# LPC1115_4TE_TOP.net
KiCad netlist of a schematic drawn in EAGLE
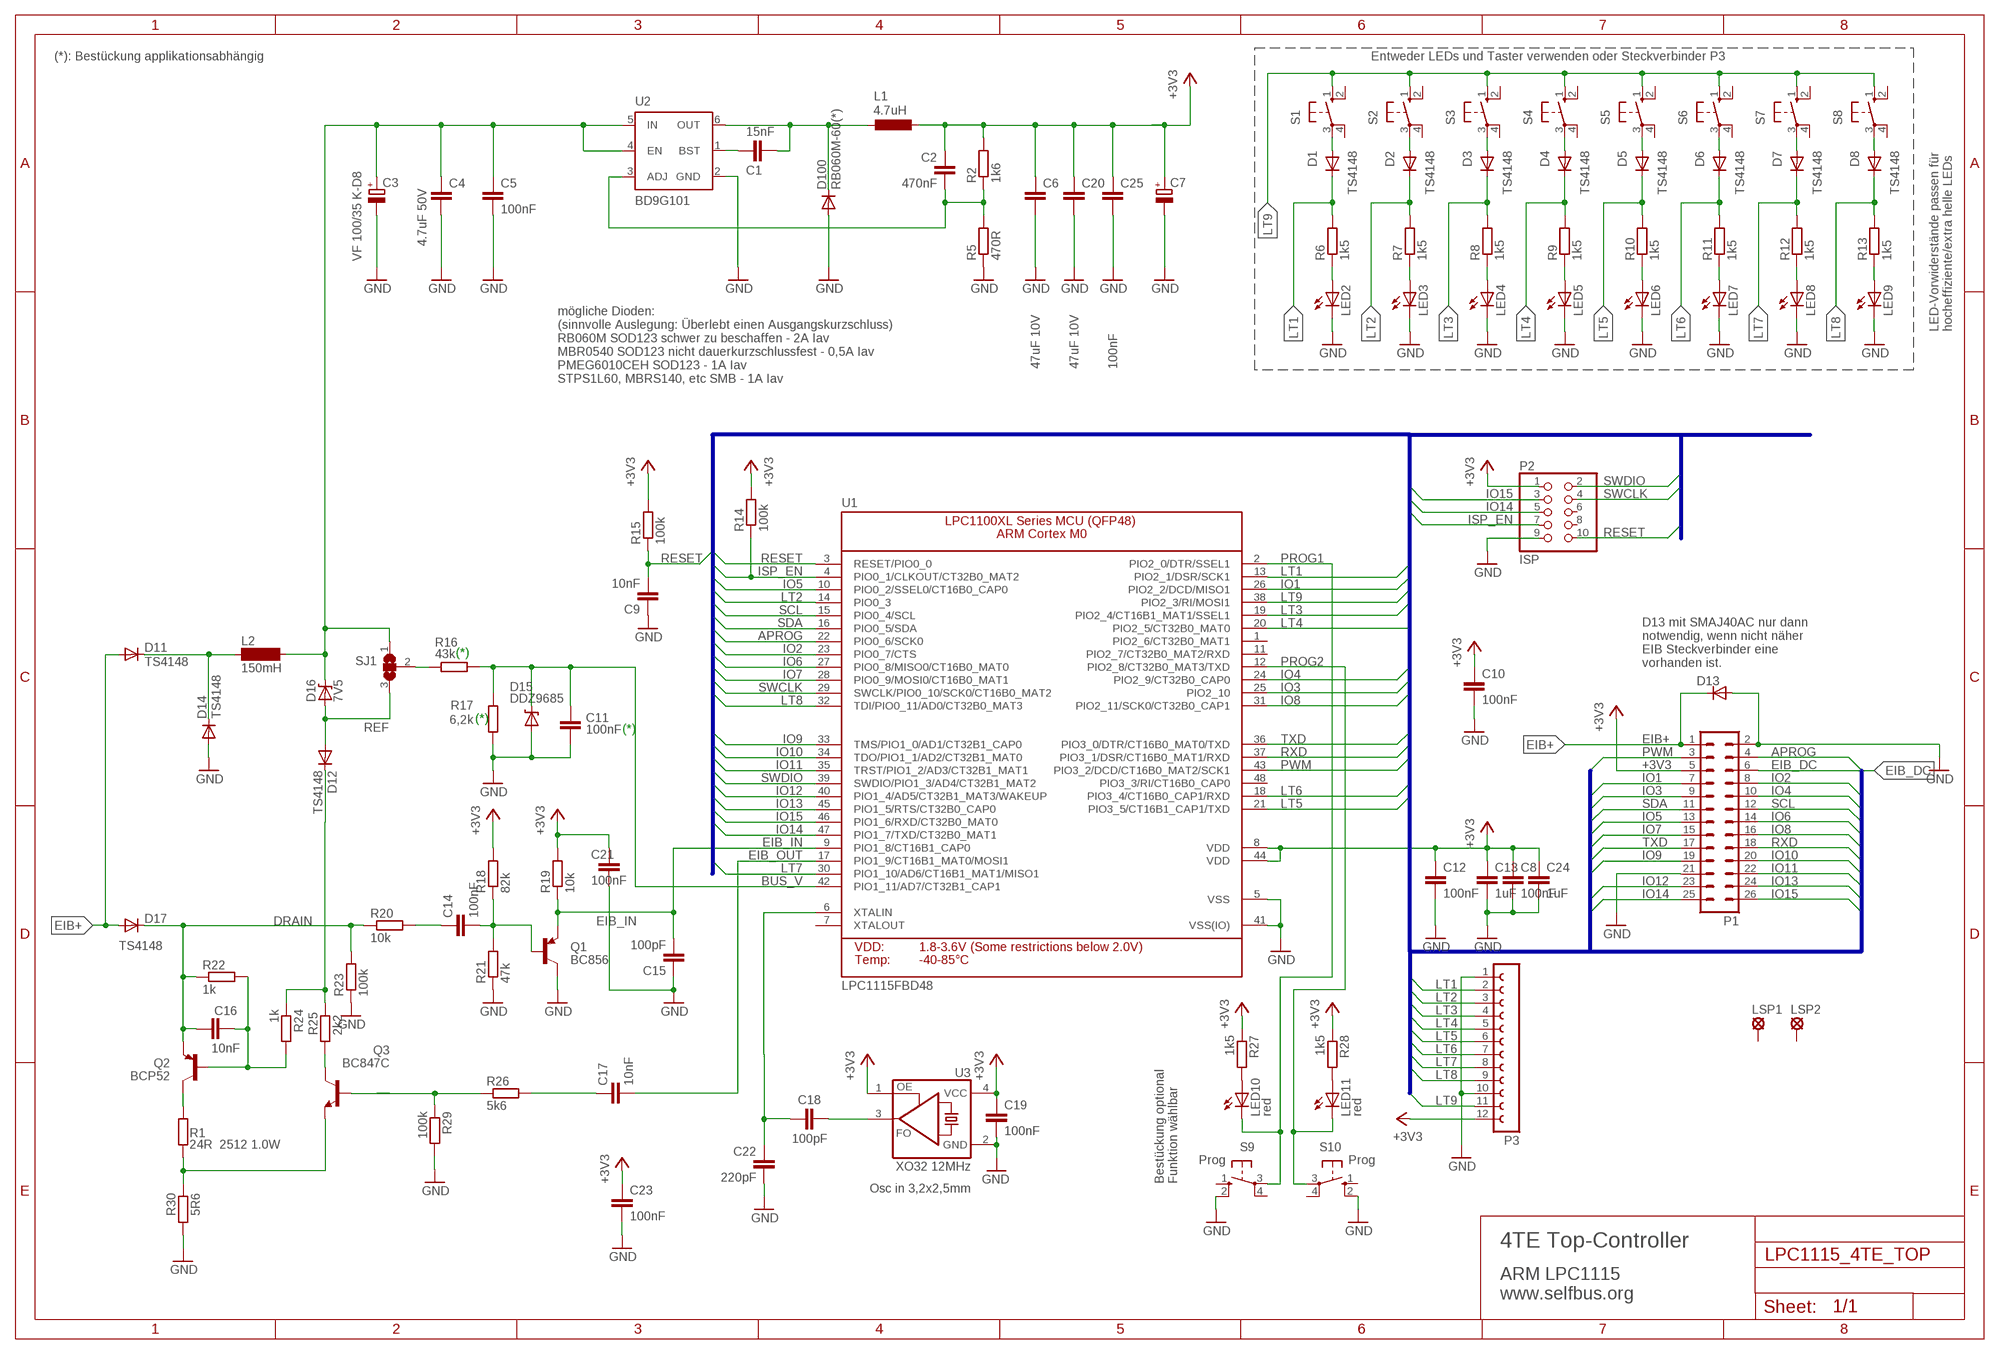
[diagram p0: schematic, sheet 1]

(export (version "E")
  (design (tool "Eeschema 10.0.6"))
  (components
    (comp (ref "C1")
      (value "15nF")
      (footprint "eagle-import:C0805")
      (libsource (lib "eagle-import") (part "C-EUC0805"))
    )
    (comp (ref "C2")
      (value "470nF")
      (footprint "eagle-import:C0805")
      (libsource (lib "eagle-import") (part "C-EUC0805"))
    )
    (comp (ref "C3")
      (value "VF 100/35 K-D8")
      (footprint "eagle-import:ESMD-D")
      (libsource (lib "eagle-import") (part "CPOL-EUESMD-D"))
    )
    (comp (ref "C4")
      (value "4.7uF 50V")
      (footprint "eagle-import:C0805")
      (libsource (lib "eagle-import") (part "C-EUC0805"))
    )
    (comp (ref "C5")
      (value "100nF")
      (footprint "eagle-import:C0805")
      (libsource (lib "eagle-import") (part "C-EUC0805"))
    )
    (comp (ref "C6")
      (value "47uF 10V")
      (footprint "eagle-import:C0805")
      (libsource (lib "eagle-import") (part "C-EUC0805"))
    )
    (comp (ref "C7")
      (value "100uF")
      (footprint "eagle-import:ESMD-D")
      (libsource (lib "eagle-import") (part "CPOL-EUESMD-D"))
    )
    (comp (ref "C8")
      (value "100nF")
      (footprint "eagle-import:C0805")
      (libsource (lib "eagle-import") (part "C-EUC0805"))
    )
    (comp (ref "C9")
      (value "10nF")
      (footprint "eagle-import:C0805")
      (libsource (lib "eagle-import") (part "C-EUC0805"))
    )
    (comp (ref "C10")
      (value "100nF")
      (footprint "eagle-import:C0805")
      (libsource (lib "eagle-import") (part "C-EUC0805"))
    )
    (comp (ref "C11")
      (value "100nF")
      (footprint "eagle-import:C0805")
      (libsource (lib "eagle-import") (part "C-EUC0805"))
    )
    (comp (ref "C12")
      (value "100nF")
      (footprint "eagle-import:C0805")
      (libsource (lib "eagle-import") (part "C-EUC0805"))
    )
    (comp (ref "C13")
      (value "1uF")
      (footprint "eagle-import:C0805")
      (libsource (lib "eagle-import") (part "C-EUC0805"))
    )
    (comp (ref "C14")
      (value "100nF")
      (footprint "eagle-import:C0805")
      (libsource (lib "eagle-import") (part "C-EUC0805"))
    )
    (comp (ref "C15")
      (value "100pF")
      (footprint "eagle-import:C0805")
      (libsource (lib "eagle-import") (part "C-EUC0805"))
    )
    (comp (ref "C16")
      (value "10nF")
      (footprint "eagle-import:C0805")
      (libsource (lib "eagle-import") (part "C-EUC0805"))
    )
    (comp (ref "C17")
      (value "10nF")
      (footprint "eagle-import:C0805")
      (libsource (lib "eagle-import") (part "C-EUC0805"))
    )
    (comp (ref "C18")
      (value "100pF")
      (footprint "eagle-import:C0805")
      (libsource (lib "eagle-import") (part "C-EUC0805"))
    )
    (comp (ref "C19")
      (value "100nF")
      (footprint "eagle-import:C0805")
      (libsource (lib "eagle-import") (part "C-EUC0805"))
    )
    (comp (ref "C20")
      (value "47uF 10V")
      (footprint "eagle-import:C0805")
      (libsource (lib "eagle-import") (part "C-EUC0805"))
    )
    (comp (ref "C21")
      (value "100nF")
      (footprint "eagle-import:C0805")
      (libsource (lib "eagle-import") (part "C-EUC0805"))
    )
    (comp (ref "C22")
      (value "220pF")
      (footprint "eagle-import:C0805")
      (libsource (lib "eagle-import") (part "C-EUC0805"))
    )
    (comp (ref "C23")
      (value "100nF")
      (footprint "eagle-import:C0805")
      (libsource (lib "eagle-import") (part "C-EUC0805"))
    )
    (comp (ref "C24")
      (value "1uF")
      (footprint "eagle-import:C0805")
      (libsource (lib "eagle-import") (part "C-EUC0805"))
    )
    (comp (ref "C25")
      (value "100nF")
      (footprint "eagle-import:C1206")
      (libsource (lib "eagle-import") (part "C-EUC1206"))
    )
    (comp (ref "D1")
      (value "TS4148")
      (footprint "eagle-import:D0805")
      (libsource (lib "eagle-import") (part "DIODE-D0805"))
    )
    (comp (ref "D2")
      (value "TS4148")
      (footprint "eagle-import:D0805")
      (libsource (lib "eagle-import") (part "DIODE-D0805"))
    )
    (comp (ref "D3")
      (value "TS4148")
      (footprint "eagle-import:D0805")
      (libsource (lib "eagle-import") (part "DIODE-D0805"))
    )
    (comp (ref "D4")
      (value "TS4148")
      (footprint "eagle-import:D0805")
      (libsource (lib "eagle-import") (part "DIODE-D0805"))
    )
    (comp (ref "D5")
      (value "TS4148")
      (footprint "eagle-import:D0805")
      (libsource (lib "eagle-import") (part "DIODE-D0805"))
    )
    (comp (ref "D6")
      (value "TS4148")
      (footprint "eagle-import:D0805")
      (libsource (lib "eagle-import") (part "DIODE-D0805"))
    )
    (comp (ref "D7")
      (value "TS4148")
      (footprint "eagle-import:D0805")
      (libsource (lib "eagle-import") (part "DIODE-D0805"))
    )
    (comp (ref "D8")
      (value "TS4148")
      (footprint "eagle-import:D0805")
      (libsource (lib "eagle-import") (part "DIODE-D0805"))
    )
    (comp (ref "D11")
      (value "TS4148")
      (footprint "eagle-import:D0805")
      (libsource (lib "eagle-import") (part "DIODE-D0805"))
    )
    (comp (ref "D12")
      (value "TS4148")
      (footprint "eagle-import:D0805")
      (libsource (lib "eagle-import") (part "DIODE-D0805"))
    )
    (comp (ref "D13")
      (value "SMAJ40AC")
      (footprint "eagle-import:SMB")
      (libsource (lib "eagle-import") (part "D-SMB"))
    )
    (comp (ref "D14")
      (value "TS4148")
      (footprint "eagle-import:D0805")
      (libsource (lib "eagle-import") (part "DIODE-D0805"))
    )
    (comp (ref "D15")
      (value "DDZ9685")
      (footprint "eagle-import:SOD-123")
      (libsource (lib "eagle-import") (part "DIODE-ZENERSOD-123"))
    )
    (comp (ref "D16")
      (value "7V5")
      (footprint "eagle-import:SOD-123")
      (libsource (lib "eagle-import") (part "DIODE-ZENERSOD-123"))
    )
    (comp (ref "D17")
      (value "TS4148")
      (footprint "eagle-import:D0805")
      (libsource (lib "eagle-import") (part "DIODE-D0805"))
    )
    (comp (ref "D100")
      (value "RB060M-60(*)")
      (footprint "eagle-import:SOD123")
      (libsource (lib "eagle-import") (part "DIODE-SOD123"))
    )
    (comp (ref "L1")
      (value "4.7uH")
      (footprint "eagle-import:L4532P")
      (libsource (lib "eagle-import") (part "L-EUL4532P"))
    )
    (comp (ref "L2")
      (value "150mH")
      (footprint "eagle-import:BS11_LIEGEND")
      (libsource (lib "eagle-import") (part "SD12BS11_LIEGEND"))
    )
    (comp (ref "LED2")
      (value "LEDSMT1206")
      (footprint "eagle-import:1206")
      (libsource (lib "eagle-import") (part "LEDSMT1206"))
    )
    (comp (ref "LED3")
      (value "LEDSMT1206")
      (footprint "eagle-import:1206")
      (libsource (lib "eagle-import") (part "LEDSMT1206"))
    )
    (comp (ref "LED4")
      (value "LEDSMT1206")
      (footprint "eagle-import:1206")
      (libsource (lib "eagle-import") (part "LEDSMT1206"))
    )
    (comp (ref "LED5")
      (value "LEDSMT1206")
      (footprint "eagle-import:1206")
      (libsource (lib "eagle-import") (part "LEDSMT1206"))
    )
    (comp (ref "LED6")
      (value "LEDSMT1206")
      (footprint "eagle-import:1206")
      (libsource (lib "eagle-import") (part "LEDSMT1206"))
    )
    (comp (ref "LED7")
      (value "LEDSMT1206")
      (footprint "eagle-import:1206")
      (libsource (lib "eagle-import") (part "LEDSMT1206"))
    )
    (comp (ref "LED8")
      (value "LEDSMT1206")
      (footprint "eagle-import:1206")
      (libsource (lib "eagle-import") (part "LEDSMT1206"))
    )
    (comp (ref "LED9")
      (value "LEDSMT1206")
      (footprint "eagle-import:1206")
      (libsource (lib "eagle-import") (part "LEDSMT1206"))
    )
    (comp (ref "LED10")
      (value "red")
      (footprint "eagle-import:1206")
      (libsource (lib "eagle-import") (part "LEDSMT1206"))
    )
    (comp (ref "LED11")
      (value "red")
      (footprint "eagle-import:1206")
      (libsource (lib "eagle-import") (part "LEDSMT1206"))
    )
    (comp (ref "LSP1")
      (value "SE13_SM")
      (footprint "eagle-import:SE13_SM")
      (libsource (lib "eagle-import") (part "SE13_SM"))
    )
    (comp (ref "LSP2")
      (value "SE13_SM")
      (footprint "eagle-import:SE13_SM")
      (libsource (lib "eagle-import") (part "SE13_SM"))
    )
    (comp (ref "P1")
      (value "ML26")
      (footprint "eagle-import:ML26")
      (libsource (lib "eagle-import") (part "ML26"))
    )
    (comp (ref "P2")
      (value "ISP")
      (footprint "eagle-import:2X05M")
      (libsource (lib "eagle-import") (part "PINHD-2X05_2.00"))
    )
    (comp (ref "P3")
      (value "FE12-1")
      (footprint "eagle-import:FE12")
      (libsource (lib "eagle-import") (part "FE12-1"))
    )
    (comp (ref "Q1")
      (value "BC856")
      (footprint "eagle-import:SOT23-BEC")
      (libsource (lib "eagle-import") (part "BC856SMDB"))
    )
    (comp (ref "Q2")
      (value "BCP52")
      (footprint "eagle-import:SOT223")
      (libsource (lib "eagle-import") (part "FZT753SMD"))
    )
    (comp (ref "Q3")
      (value "BC847C")
      (footprint "eagle-import:SOT23")
      (libsource (lib "eagle-import") (part "BC847"))
    )
    (comp (ref "R1")
      (value "24R 2512 1.0W")
      (footprint "eagle-import:R2512")
      (libsource (lib "eagle-import") (part "R-EU_R2512"))
    )
    (comp (ref "R2")
      (value "1k6")
      (footprint "eagle-import:R0805")
      (libsource (lib "eagle-import") (part "R-EU_R0805"))
    )
    (comp (ref "R5")
      (value "470R")
      (footprint "eagle-import:R0805")
      (libsource (lib "eagle-import") (part "R-EU_R0805"))
    )
    (comp (ref "R6")
      (value "1k5")
      (footprint "eagle-import:R0805")
      (libsource (lib "eagle-import") (part "R-EU_R0805"))
    )
    (comp (ref "R7")
      (value "1k5")
      (footprint "eagle-import:R0805")
      (libsource (lib "eagle-import") (part "R-EU_R0805"))
    )
    (comp (ref "R8")
      (value "1k5")
      (footprint "eagle-import:R0805")
      (libsource (lib "eagle-import") (part "R-EU_R0805"))
    )
    (comp (ref "R9")
      (value "1k5")
      (footprint "eagle-import:R0805")
      (libsource (lib "eagle-import") (part "R-EU_R0805"))
    )
    (comp (ref "R10")
      (value "1k5")
      (footprint "eagle-import:R0805")
      (libsource (lib "eagle-import") (part "R-EU_R0805"))
    )
    (comp (ref "R11")
      (value "1k5")
      (footprint "eagle-import:R0805")
      (libsource (lib "eagle-import") (part "R-EU_R0805"))
    )
    (comp (ref "R12")
      (value "1k5")
      (footprint "eagle-import:R0805")
      (libsource (lib "eagle-import") (part "R-EU_R0805"))
    )
    (comp (ref "R13")
      (value "1k5")
      (footprint "eagle-import:R0805")
      (libsource (lib "eagle-import") (part "R-EU_R0805"))
    )
    (comp (ref "R14")
      (value "100k")
      (footprint "eagle-import:R0805")
      (libsource (lib "eagle-import") (part "R-EU_R0805"))
    )
    (comp (ref "R15")
      (value "100k")
      (footprint "eagle-import:R0805")
      (libsource (lib "eagle-import") (part "R-EU_R0805"))
    )
    (comp (ref "R16")
      (value "43k")
      (footprint "eagle-import:R0805")
      (libsource (lib "eagle-import") (part "R-EU_R0805"))
    )
    (comp (ref "R17")
      (value "6,2k")
      (footprint "eagle-import:R0805")
      (libsource (lib "eagle-import") (part "R-EU_R0805"))
    )
    (comp (ref "R18")
      (value "82k")
      (footprint "eagle-import:R0805")
      (libsource (lib "eagle-import") (part "R-EU_R0805"))
    )
    (comp (ref "R19")
      (value "10k")
      (footprint "eagle-import:R0805")
      (libsource (lib "eagle-import") (part "R-EU_R0805"))
    )
    (comp (ref "R20")
      (value "10k")
      (footprint "eagle-import:R0805")
      (libsource (lib "eagle-import") (part "R-EU_R0805"))
    )
    (comp (ref "R21")
      (value "47k")
      (footprint "eagle-import:R0805")
      (libsource (lib "eagle-import") (part "R-EU_R0805"))
    )
    (comp (ref "R22")
      (value "1k")
      (footprint "eagle-import:R0805")
      (libsource (lib "eagle-import") (part "R-EU_R0805"))
    )
    (comp (ref "R23")
      (value "100k")
      (footprint "eagle-import:R0805")
      (libsource (lib "eagle-import") (part "R-EU_R0805"))
    )
    (comp (ref "R24")
      (value "1k")
      (footprint "eagle-import:R0805")
      (libsource (lib "eagle-import") (part "R-EU_R0805"))
    )
    (comp (ref "R25")
      (value "2k2")
      (footprint "eagle-import:R0805")
      (libsource (lib "eagle-import") (part "R-EU_R0805"))
    )
    (comp (ref "R26")
      (value "5k6")
      (footprint "eagle-import:R0805")
      (libsource (lib "eagle-import") (part "R-EU_R0805"))
    )
    (comp (ref "R27")
      (value "1k5")
      (footprint "eagle-import:R0805")
      (libsource (lib "eagle-import") (part "R-EU_R0805"))
    )
    (comp (ref "R28")
      (value "1k5")
      (footprint "eagle-import:R0805")
      (libsource (lib "eagle-import") (part "R-EU_R0805"))
    )
    (comp (ref "R29")
      (value "100k")
      (footprint "eagle-import:R0805")
      (libsource (lib "eagle-import") (part "R-EU_R0805"))
    )
    (comp (ref "R30")
      (value "5R6")
      (footprint "eagle-import:R0805")
      (libsource (lib "eagle-import") (part "R-EU_R0805"))
    )
    (comp (ref "S1")
      (value "10-XXSMD")
      (footprint "eagle-import:B3F-10XX_SMD")
      (libsource (lib "eagle-import") (part "10-XXSMD"))
    )
    (comp (ref "S2")
      (value "10-XXSMD")
      (footprint "eagle-import:B3F-10XX_SMD")
      (libsource (lib "eagle-import") (part "10-XXSMD"))
    )
    (comp (ref "S3")
      (value "10-XXSMD")
      (footprint "eagle-import:B3F-10XX_SMD")
      (libsource (lib "eagle-import") (part "10-XXSMD"))
    )
    (comp (ref "S4")
      (value "10-XXSMD")
      (footprint "eagle-import:B3F-10XX_SMD")
      (libsource (lib "eagle-import") (part "10-XXSMD"))
    )
    (comp (ref "S5")
      (value "10-XXSMD")
      (footprint "eagle-import:B3F-10XX_SMD")
      (libsource (lib "eagle-import") (part "10-XXSMD"))
    )
    (comp (ref "S6")
      (value "10-XXSMD")
      (footprint "eagle-import:B3F-10XX_SMD")
      (libsource (lib "eagle-import") (part "10-XXSMD"))
    )
    (comp (ref "S7")
      (value "10-XXSMD")
      (footprint "eagle-import:B3F-10XX_SMD")
      (libsource (lib "eagle-import") (part "10-XXSMD"))
    )
    (comp (ref "S8")
      (value "10-XXSMD")
      (footprint "eagle-import:B3F-10XX_SMD")
      (libsource (lib "eagle-import") (part "10-XXSMD"))
    )
    (comp (ref "S9")
      (value "Prog")
      (footprint "eagle-import:B3F-10XX_SMD")
      (libsource (lib "eagle-import") (part "10-XXSMD"))
    )
    (comp (ref "S10")
      (value "Prog")
      (footprint "eagle-import:B3F-10XX_SMD")
      (libsource (lib "eagle-import") (part "10-XXSMD"))
    )
    (comp (ref "SJ1")
      (value "SJ2W")
      (footprint "eagle-import:SJ_2")
      (libsource (lib "eagle-import") (part "SJ2W"))
    )
    (comp (ref "U1")
      (value "LPC1115FBD48")
      (footprint "eagle-import:LQFP48")
      (libsource (lib "eagle-import") (part "LPC1113/4/5_QFP48_XLSERIES"))
    )
    (comp (ref "U2")
      (value "BD9G101")
      (footprint "eagle-import:SOT23-6MOD")
      (libsource (lib "eagle-import") (part "BD9G101GBD9G101G-SOT23-6MOD"))
    )
    (comp (ref "U3")
      (value "XO32 12MHz")
      (footprint "eagle-import:ASF")
      (libsource (lib "eagle-import") (part "ASFL"))
    )
  )
  (nets
    (net (code "1") (name "+3V3") (class "Default")
      (node (ref "C10") (pin "1") (pinfunction "1_1") (pintype "passive"))
      (node (ref "C12") (pin "1") (pinfunction "1_1") (pintype "passive"))
      (node (ref "C13") (pin "1") (pinfunction "1_1") (pintype "passive"))
      (node (ref "C19") (pin "1") (pinfunction "1_1") (pintype "passive"))
      (node (ref "C2") (pin "1") (pinfunction "1_1") (pintype "passive"))
      (node (ref "C20") (pin "1") (pinfunction "1_1") (pintype "passive"))
      (node (ref "C21") (pin "2") (pinfunction "2_2") (pintype "passive"))
      (node (ref "C23") (pin "1") (pinfunction "1_1") (pintype "passive"))
      (node (ref "C24") (pin "1") (pinfunction "1_1") (pintype "passive"))
      (node (ref "C25") (pin "1") (pinfunction "1_1") (pintype "passive"))
      (node (ref "C6") (pin "1") (pinfunction "1_1") (pintype "passive"))
      (node (ref "C7") (pin "+") (pinfunction "+_+") (pintype "passive"))
      (node (ref "C8") (pin "1") (pinfunction "1_1") (pintype "passive"))
      (node (ref "L1") (pin "2") (pinfunction "2_2") (pintype "passive"))
      (node (ref "P1") (pin "5") (pinfunction "5_5") (pintype "passive"))
      (node (ref "P2") (pin "1") (pinfunction "1_1") (pintype "passive"))
      (node (ref "P3") (pin "12") (pinfunction "12_12") (pintype "passive"))
      (node (ref "R14") (pin "2") (pinfunction "2_2") (pintype "passive"))
      (node (ref "R15") (pin "2") (pinfunction "2_2") (pintype "passive"))
      (node (ref "R18") (pin "2") (pinfunction "2_2") (pintype "passive"))
      (node (ref "R19") (pin "2") (pinfunction "2_2") (pintype "passive"))
      (node (ref "R2") (pin "2") (pinfunction "2_2") (pintype "passive"))
      (node (ref "R27") (pin "1") (pinfunction "1_1") (pintype "passive"))
      (node (ref "R28") (pin "1") (pinfunction "1_1") (pintype "passive"))
      (node (ref "U1") (pin "44") (pinfunction "VDD_44") (pintype "power_in"))
      (node (ref "U1") (pin "8") (pinfunction "VDD_8") (pintype "power_in"))
      (node (ref "U3") (pin "1") (pinfunction "OE_1") (pintype "input"))
      (node (ref "U3") (pin "4") (pinfunction "VCC_4") (pintype "power_in"))
    )
    (net (code "2") (name "/APROG") (class "Default")
      (node (ref "P1") (pin "4") (pinfunction "4_4") (pintype "passive"))
      (node (ref "U1") (pin "22") (pinfunction "PIO0_6/SCK0_22") (pintype "bidirectional"))
    )
    (net (code "3") (name "/BUS_V") (class "Default")
      (node (ref "C11") (pin "1") (pinfunction "1_1") (pintype "passive"))
      (node (ref "D15") (pin "C") (pinfunction "C_C") (pintype "passive"))
      (node (ref "R16") (pin "2") (pinfunction "2_2") (pintype "passive"))
      (node (ref "R17") (pin "1") (pinfunction "1_1") (pintype "passive"))
      (node (ref "U1") (pin "42") (pinfunction "PIO1_11/AD7/CT32B1_CAP1_42") (pintype "bidirectional"))
    )
    (net (code "4") (name "/DRAIN") (class "Default")
      (node (ref "C16") (pin "1") (pinfunction "1_1") (pintype "passive"))
      (node (ref "D17") (pin "C") (pinfunction "C_C") (pintype "passive"))
      (node (ref "Q2") (pin "3") (pinfunction "E_3") (pintype "passive"))
      (node (ref "R20") (pin "1") (pinfunction "1_1") (pintype "passive"))
      (node (ref "R22") (pin "1") (pinfunction "1_1") (pintype "passive"))
      (node (ref "R23") (pin "2") (pinfunction "2_2") (pintype "passive"))
    )
    (net (code "5") (name "/EIB_IN") (class "Default")
      (node (ref "C15") (pin "2") (pinfunction "2_2") (pintype "passive"))
      (node (ref "Q1") (pin "E") (pinfunction "E_E") (pintype "passive"))
      (node (ref "R19") (pin "1") (pinfunction "1_1") (pintype "passive"))
      (node (ref "U1") (pin "9") (pinfunction "PIO1_8/CT16B1_CAP0_9") (pintype "bidirectional"))
    )
    (net (code "6") (name "/EIB_OUT") (class "Default")
      (node (ref "C17") (pin "2") (pinfunction "2_2") (pintype "passive"))
      (node (ref "U1") (pin "17") (pinfunction "PIO1_9/CT16B1_MAT0/MOSI1_17") (pintype "bidirectional"))
    )
    (net (code "7") (name "/IO1") (class "Default")
      (node (ref "P1") (pin "7") (pinfunction "7_7") (pintype "passive"))
      (node (ref "U1") (pin "26") (pinfunction "PIO2_2/DCD/MISO1_26") (pintype "bidirectional"))
    )
    (net (code "8") (name "/IO2") (class "Default")
      (node (ref "P1") (pin "8") (pinfunction "8_8") (pintype "passive"))
      (node (ref "U1") (pin "23") (pinfunction "PIO0_7/CTS_23") (pintype "bidirectional"))
    )
    (net (code "9") (name "/IO3") (class "Default")
      (node (ref "P1") (pin "9") (pinfunction "9_9") (pintype "passive"))
      (node (ref "U1") (pin "25") (pinfunction "PIO2_10_25") (pintype "bidirectional"))
    )
    (net (code "10") (name "/IO4") (class "Default")
      (node (ref "P1") (pin "10") (pinfunction "10_10") (pintype "passive"))
      (node (ref "U1") (pin "24") (pinfunction "PIO2_9/CT32B0_CAP0_24") (pintype "bidirectional"))
    )
    (net (code "11") (name "/IO5") (class "Default")
      (node (ref "P1") (pin "13") (pinfunction "13_13") (pintype "passive"))
      (node (ref "U1") (pin "10") (pinfunction "PIO0_2/SSEL0/CT16B0_CAP0_10") (pintype "bidirectional"))
    )
    (net (code "12") (name "/IO6") (class "Default")
      (node (ref "P1") (pin "14") (pinfunction "14_14") (pintype "passive"))
      (node (ref "U1") (pin "27") (pinfunction "PIO0_8/MISO0/CT16B0_MAT0_27") (pintype "bidirectional"))
    )
    (net (code "13") (name "/IO7") (class "Default")
      (node (ref "P1") (pin "15") (pinfunction "15_15") (pintype "passive"))
      (node (ref "U1") (pin "28") (pinfunction "PIO0_9/MOSI0/CT16B0_MAT1_28") (pintype "bidirectional"))
    )
    (net (code "14") (name "/IO8") (class "Default")
      (node (ref "P1") (pin "16") (pinfunction "16_16") (pintype "passive"))
      (node (ref "U1") (pin "31") (pinfunction "PIO2_11/SCK0/CT32B0_CAP1_31") (pintype "bidirectional"))
    )
    (net (code "15") (name "/IO9") (class "Default")
      (node (ref "P1") (pin "19") (pinfunction "19_19") (pintype "passive"))
      (node (ref "U1") (pin "33") (pinfunction "TMS/PIO1_0/AD1/CT32B1_CAP0_33") (pintype "bidirectional"))
    )
    (net (code "16") (name "/IO10") (class "Default")
      (node (ref "P1") (pin "20") (pinfunction "20_20") (pintype "passive"))
      (node (ref "U1") (pin "34") (pinfunction "TDO/PIO1_1/AD2/CT32B1_MAT0_34") (pintype "bidirectional"))
    )
    (net (code "17") (name "/IO11") (class "Default")
      (node (ref "P1") (pin "22") (pinfunction "22_22") (pintype "passive"))
      (node (ref "U1") (pin "35") (pinfunction "TRST/PIO1_2/AD3/CT32B1_MAT1_35") (pintype "bidirectional"))
    )
    (net (code "18") (name "/IO12") (class "Default")
      (node (ref "P1") (pin "23") (pinfunction "23_23") (pintype "passive"))
      (node (ref "U1") (pin "40") (pinfunction "PIO1_4/AD5/CT32B1_MAT3/WAKEUP_40") (pintype "bidirectional"))
    )
    (net (code "19") (name "/IO13") (class "Default")
      (node (ref "P1") (pin "24") (pinfunction "24_24") (pintype "passive"))
      (node (ref "U1") (pin "45") (pinfunction "PIO1_5/RTS/CT32B0_CAP0_45") (pintype "bidirectional"))
    )
    (net (code "20") (name "/IO14") (class "Default")
      (node (ref "P1") (pin "25") (pinfunction "25_25") (pintype "passive"))
      (node (ref "P2") (pin "5") (pinfunction "5_5") (pintype "passive"))
      (node (ref "U1") (pin "47") (pinfunction "PIO1_7/TXD/CT32B0_MAT1_47") (pintype "bidirectional"))
    )
    (net (code "21") (name "/IO15") (class "Default")
      (node (ref "P1") (pin "26") (pinfunction "26_26") (pintype "passive"))
      (node (ref "P2") (pin "3") (pinfunction "3_3") (pintype "passive"))
      (node (ref "U1") (pin "46") (pinfunction "PIO1_6/RXD/CT32B0_MAT0_46") (pintype "bidirectional"))
    )
    (net (code "22") (name "/ISP_EN") (class "Default")
      (node (ref "P2") (pin "7") (pinfunction "7_7") (pintype "passive"))
      (node (ref "R14") (pin "1") (pinfunction "1_1") (pintype "passive"))
      (node (ref "U1") (pin "4") (pinfunction "PIO0_1/CLKOUT/CT32B0_MAT2_4") (pintype "bidirectional"))
    )
    (net (code "23") (name "/PROG1") (class "Default")
      (node (ref "LED10") (pin "C") (pinfunction "C_C") (pintype "passive"))
      (node (ref "S9") (pin "3") (pinfunction "P_3") (pintype "passive"))
      (node (ref "U1") (pin "2") (pinfunction "PIO2_0/DTR/SSEL1_2") (pintype "bidirectional"))
    )
    (net (code "24") (name "/PROG2") (class "Default")
      (node (ref "LED11") (pin "C") (pinfunction "C_C") (pintype "passive"))
      (node (ref "S10") (pin "3") (pinfunction "P_3") (pintype "passive"))
      (node (ref "U1") (pin "12") (pinfunction "PIO2_8/CT32B0_MAT3/TXD_12") (pintype "bidirectional"))
    )
    (net (code "25") (name "/PWM") (class "Default")
      (node (ref "P1") (pin "3") (pinfunction "3_3") (pintype "passive"))
      (node (ref "U1") (pin "43") (pinfunction "PIO3_2/DCD/CT16B0_MAT2/SCK1_43") (pintype "bidirectional"))
    )
    (net (code "26") (name "/REF") (class "Default")
      (node (ref "D12") (pin "A") (pinfunction "A_A") (pintype "passive"))
      (node (ref "D16") (pin "A") (pinfunction "A_A") (pintype "passive"))
      (node (ref "SJ1") (pin "3") (pinfunction "3_3") (pintype "passive"))
    )
    (net (code "27") (name "/RESET") (class "Default")
      (node (ref "C9") (pin "2") (pinfunction "2_2") (pintype "passive"))
      (node (ref "P2") (pin "10") (pinfunction "10_10") (pintype "passive"))
      (node (ref "R15") (pin "1") (pinfunction "1_1") (pintype "passive"))
      (node (ref "U1") (pin "3") (pinfunction "RESET/PIO0_0_3") (pintype "bidirectional"))
    )
    (net (code "28") (name "/RXD") (class "Default")
      (node (ref "P1") (pin "18") (pinfunction "18_18") (pintype "passive"))
      (node (ref "U1") (pin "37") (pinfunction "PIO3_1/DSR/CT16B0_MAT1/RXD_37") (pintype "bidirectional"))
    )
    (net (code "29") (name "/SCL") (class "Default")
      (node (ref "P1") (pin "12") (pinfunction "12_12") (pintype "passive"))
      (node (ref "U1") (pin "15") (pinfunction "PIO0_4/SCL_15") (pintype "bidirectional"))
    )
    (net (code "30") (name "/SDA") (class "Default")
      (node (ref "P1") (pin "11") (pinfunction "11_11") (pintype "passive"))
      (node (ref "U1") (pin "16") (pinfunction "PIO0_5/SDA_16") (pintype "bidirectional"))
    )
    (net (code "31") (name "/SWCLK") (class "Default")
      (node (ref "P2") (pin "4") (pinfunction "4_4") (pintype "passive"))
      (node (ref "U1") (pin "29") (pinfunction "SWCLK/PIO0_10/SCK0/CT16B0_MAT2_29") (pintype "bidirectional"))
    )
    (net (code "32") (name "/SWDIO") (class "Default")
      (node (ref "P2") (pin "2") (pinfunction "2_2") (pintype "passive"))
      (node (ref "U1") (pin "39") (pinfunction "SWDIO/PIO1_3/AD4/CT32B1_MAT2_39") (pintype "bidirectional"))
    )
    (net (code "33") (name "/TXD") (class "Default")
      (node (ref "P1") (pin "17") (pinfunction "17_17") (pintype "passive"))
      (node (ref "U1") (pin "36") (pinfunction "PIO3_0/DTR/CT16B0_MAT0/TXD_36") (pintype "bidirectional"))
    )
    (net (code "34") (name "EIB+") (class "Default")
      (node (ref "D11") (pin "A") (pinfunction "A_A") (pintype "passive"))
      (node (ref "D13") (pin "1") (pinfunction "C_1") (pintype "passive"))
      (node (ref "D17") (pin "A") (pinfunction "A_A") (pintype "passive"))
      (node (ref "P1") (pin "1") (pinfunction "1_1") (pintype "passive"))
    )
    (net (code "35") (name "EIB_DC") (class "Default")
      (node (ref "C3") (pin "+") (pinfunction "+_+") (pintype "passive"))
      (node (ref "C4") (pin "1") (pinfunction "1_1") (pintype "passive"))
      (node (ref "C5") (pin "1") (pinfunction "1_1") (pintype "passive"))
      (node (ref "D16") (pin "C") (pinfunction "C_C") (pintype "passive"))
      (node (ref "L2") (pin "2") (pinfunction "2_2") (pintype "passive"))
      (node (ref "P1") (pin "6") (pinfunction "6_6") (pintype "passive"))
      (node (ref "SJ1") (pin "1") (pinfunction "1_1") (pintype "passive"))
      (node (ref "U2") (pin "4") (pinfunction "EN_4") (pintype "input"))
      (node (ref "U2") (pin "5") (pinfunction "IN_5") (pintype "input"))
    )
    (net (code "36") (name "GND") (class "Default")
      (node (ref "C10") (pin "2") (pinfunction "2_2") (pintype "passive"))
      (node (ref "C11") (pin "2") (pinfunction "2_2") (pintype "passive"))
      (node (ref "C12") (pin "2") (pinfunction "2_2") (pintype "passive"))
      (node (ref "C13") (pin "2") (pinfunction "2_2") (pintype "passive"))
      (node (ref "C15") (pin "1") (pinfunction "1_1") (pintype "passive"))
      (node (ref "C19") (pin "2") (pinfunction "2_2") (pintype "passive"))
      (node (ref "C20") (pin "2") (pinfunction "2_2") (pintype "passive"))
      (node (ref "C21") (pin "1") (pinfunction "1_1") (pintype "passive"))
      (node (ref "C22") (pin "2") (pinfunction "2_2") (pintype "passive"))
      (node (ref "C23") (pin "2") (pinfunction "2_2") (pintype "passive"))
      (node (ref "C24") (pin "2") (pinfunction "2_2") (pintype "passive"))
      (node (ref "C25") (pin "2") (pinfunction "2_2") (pintype "passive"))
      (node (ref "C3") (pin "-") (pinfunction "-_-") (pintype "passive"))
      (node (ref "C4") (pin "2") (pinfunction "2_2") (pintype "passive"))
      (node (ref "C5") (pin "2") (pinfunction "2_2") (pintype "passive"))
      (node (ref "C6") (pin "2") (pinfunction "2_2") (pintype "passive"))
      (node (ref "C7") (pin "-") (pinfunction "-_-") (pintype "passive"))
      (node (ref "C8") (pin "2") (pinfunction "2_2") (pintype "passive"))
      (node (ref "C9") (pin "1") (pinfunction "1_1") (pintype "passive"))
      (node (ref "D100") (pin "A") (pinfunction "A_A") (pintype "passive"))
      (node (ref "D13") (pin "2") (pinfunction "A_2") (pintype "passive"))
      (node (ref "D14") (pin "A") (pinfunction "A_A") (pintype "passive"))
      (node (ref "D15") (pin "A") (pinfunction "A_A") (pintype "passive"))
      (node (ref "LED2") (pin "C") (pinfunction "C_C") (pintype "passive"))
      (node (ref "LED3") (pin "C") (pinfunction "C_C") (pintype "passive"))
      (node (ref "LED4") (pin "C") (pinfunction "C_C") (pintype "passive"))
      (node (ref "LED5") (pin "C") (pinfunction "C_C") (pintype "passive"))
      (node (ref "LED6") (pin "C") (pinfunction "C_C") (pintype "passive"))
      (node (ref "LED7") (pin "C") (pinfunction "C_C") (pintype "passive"))
      (node (ref "LED8") (pin "C") (pinfunction "C_C") (pintype "passive"))
      (node (ref "LED9") (pin "C") (pinfunction "C_C") (pintype "passive"))
      (node (ref "P1") (pin "2") (pinfunction "2_2") (pintype "passive"))
      (node (ref "P1") (pin "21") (pinfunction "21_21") (pintype "passive"))
      (node (ref "P2") (pin "9") (pinfunction "9_9") (pintype "passive"))
      (node (ref "P3") (pin "1") (pinfunction "1_1") (pintype "passive"))
      (node (ref "P3") (pin "10") (pinfunction "10_10") (pintype "passive"))
      (node (ref "Q1") (pin "C") (pinfunction "C_C") (pintype "passive"))
      (node (ref "R17") (pin "2") (pinfunction "2_2") (pintype "passive"))
      (node (ref "R21") (pin "1") (pinfunction "1_1") (pintype "passive"))
      (node (ref "R23") (pin "1") (pinfunction "1_1") (pintype "passive"))
      (node (ref "R29") (pin "2") (pinfunction "2_2") (pintype "passive"))
      (node (ref "R30") (pin "1") (pinfunction "1_1") (pintype "passive"))
      (node (ref "R5") (pin "1") (pinfunction "1_1") (pintype "passive"))
      (node (ref "S10") (pin "2") (pinfunction "S1_2") (pintype "passive"))
      (node (ref "S9") (pin "2") (pinfunction "S1_2") (pintype "passive"))
      (node (ref "U1") (pin "41") (pinfunction "VSS(IO)_41") (pintype "power_in"))
      (node (ref "U1") (pin "5") (pinfunction "VSS_5") (pintype "power_in"))
      (node (ref "U2") (pin "2") (pinfunction "GND_2") (pintype "power_in"))
      (node (ref "U3") (pin "2") (pinfunction "GND_2") (pintype "power_in"))
    )
    (net (code "37") (name "LT1") (class "Default")
      (node (ref "D1") (pin "C") (pinfunction "C_C") (pintype "passive"))
      (node (ref "P3") (pin "2") (pinfunction "2_2") (pintype "passive"))
      (node (ref "R6") (pin "2") (pinfunction "2_2") (pintype "passive"))
      (node (ref "U1") (pin "13") (pinfunction "PIO2_1/DSR/SCK1_13") (pintype "bidirectional"))
    )
    (net (code "38") (name "LT2") (class "Default")
      (node (ref "D2") (pin "C") (pinfunction "C_C") (pintype "passive"))
      (node (ref "P3") (pin "3") (pinfunction "3_3") (pintype "passive"))
      (node (ref "R7") (pin "2") (pinfunction "2_2") (pintype "passive"))
      (node (ref "U1") (pin "14") (pinfunction "PIO0_3_14") (pintype "bidirectional"))
    )
    (net (code "39") (name "LT3") (class "Default")
      (node (ref "D3") (pin "C") (pinfunction "C_C") (pintype "passive"))
      (node (ref "P3") (pin "4") (pinfunction "4_4") (pintype "passive"))
      (node (ref "R8") (pin "2") (pinfunction "2_2") (pintype "passive"))
      (node (ref "U1") (pin "19") (pinfunction "PIO2_4/CT16B1_MAT1/SSEL1_19") (pintype "bidirectional"))
    )
    (net (code "40") (name "LT4") (class "Default")
      (node (ref "D4") (pin "C") (pinfunction "C_C") (pintype "passive"))
      (node (ref "P3") (pin "5") (pinfunction "5_5") (pintype "passive"))
      (node (ref "R9") (pin "2") (pinfunction "2_2") (pintype "passive"))
      (node (ref "U1") (pin "20") (pinfunction "PIO2_5/CT32B0_MAT0_20") (pintype "bidirectional"))
    )
    (net (code "41") (name "LT5") (class "Default")
      (node (ref "D5") (pin "C") (pinfunction "C_C") (pintype "passive"))
      (node (ref "P3") (pin "6") (pinfunction "6_6") (pintype "passive"))
      (node (ref "R10") (pin "2") (pinfunction "2_2") (pintype "passive"))
      (node (ref "U1") (pin "21") (pinfunction "PIO3_5/CT16B1_CAP1/TXD_21") (pintype "bidirectional"))
    )
    (net (code "42") (name "LT6") (class "Default")
      (node (ref "D6") (pin "C") (pinfunction "C_C") (pintype "passive"))
      (node (ref "P3") (pin "7") (pinfunction "7_7") (pintype "passive"))
      (node (ref "R11") (pin "2") (pinfunction "2_2") (pintype "passive"))
      (node (ref "U1") (pin "18") (pinfunction "PIO3_4/CT16B0_CAP1/RXD_18") (pintype "bidirectional"))
    )
    (net (code "43") (name "LT7") (class "Default")
      (node (ref "D7") (pin "C") (pinfunction "C_C") (pintype "passive"))
      (node (ref "P3") (pin "8") (pinfunction "8_8") (pintype "passive"))
      (node (ref "R12") (pin "2") (pinfunction "2_2") (pintype "passive"))
      (node (ref "U1") (pin "30") (pinfunction "PIO1_10/AD6/CT16B1_MAT1/MISO1_30") (pintype "bidirectional"))
    )
    (net (code "44") (name "LT8") (class "Default")
      (node (ref "D8") (pin "C") (pinfunction "C_C") (pintype "passive"))
      (node (ref "P3") (pin "9") (pinfunction "9_9") (pintype "passive"))
      (node (ref "R13") (pin "2") (pinfunction "2_2") (pintype "passive"))
      (node (ref "U1") (pin "32") (pinfunction "TDI/PIO0_11/AD0/CT32B0_MAT3_32") (pintype "bidirectional"))
    )
    (net (code "45") (name "LT9") (class "Default")
      (node (ref "P3") (pin "11") (pinfunction "11_11") (pintype "passive"))
      (node (ref "S1") (pin "1") (pinfunction "S_1") (pintype "passive"))
      (node (ref "S2") (pin "1") (pinfunction "S_1") (pintype "passive"))
      (node (ref "S3") (pin "1") (pinfunction "S_1") (pintype "passive"))
      (node (ref "S4") (pin "1") (pinfunction "S_1") (pintype "passive"))
      (node (ref "S5") (pin "1") (pinfunction "S_1") (pintype "passive"))
      (node (ref "S6") (pin "1") (pinfunction "S_1") (pintype "passive"))
      (node (ref "S7") (pin "1") (pinfunction "S_1") (pintype "passive"))
      (node (ref "S8") (pin "1") (pinfunction "S_1") (pintype "passive"))
      (node (ref "U1") (pin "38") (pinfunction "PIO2_3/RI/MOSI1_38") (pintype "bidirectional"))
    )
    (net (code "46") (name "Net-(C14-Pad1)") (class "Default")
      (node (ref "C14") (pin "1") (pinfunction "1_1") (pintype "passive"))
      (node (ref "R20") (pin "2") (pinfunction "2_2") (pintype "passive"))
    )
    (net (code "47") (name "Net-(C14-Pad2)") (class "Default")
      (node (ref "C14") (pin "2") (pinfunction "2_2") (pintype "passive"))
      (node (ref "Q1") (pin "B") (pinfunction "B_B") (pintype "passive"))
      (node (ref "R18") (pin "1") (pinfunction "1_1") (pintype "passive"))
      (node (ref "R21") (pin "2") (pinfunction "2_2") (pintype "passive"))
    )
    (net (code "48") (name "Net-(C17-Pad1)") (class "Default")
      (node (ref "C17") (pin "1") (pinfunction "1_1") (pintype "passive"))
      (node (ref "R26") (pin "2") (pinfunction "2_2") (pintype "passive"))
    )
    (net (code "49") (name "Net-(D11-PadC)") (class "Default")
      (node (ref "D11") (pin "C") (pinfunction "C_C") (pintype "passive"))
      (node (ref "D14") (pin "C") (pinfunction "C_C") (pintype "passive"))
      (node (ref "L2") (pin "1") (pinfunction "1_1") (pintype "passive"))
    )
    (net (code "50") (name "Net-(D12-PadC)") (class "Default")
      (node (ref "D12") (pin "C") (pinfunction "C_C") (pintype "passive"))
      (node (ref "R24") (pin "1") (pinfunction "1_1") (pintype "passive"))
      (node (ref "R25") (pin "2") (pinfunction "2_2") (pintype "passive"))
    )
    (net (code "51") (name "Net-(LED2-PadA)") (class "Default")
      (node (ref "LED2") (pin "A") (pinfunction "A_A") (pintype "passive"))
      (node (ref "R6") (pin "1") (pinfunction "1_1") (pintype "passive"))
    )
    (net (code "52") (name "Net-(LED3-PadA)") (class "Default")
      (node (ref "LED3") (pin "A") (pinfunction "A_A") (pintype "passive"))
      (node (ref "R7") (pin "1") (pinfunction "1_1") (pintype "passive"))
    )
    (net (code "53") (name "Net-(LED4-PadA)") (class "Default")
      (node (ref "LED4") (pin "A") (pinfunction "A_A") (pintype "passive"))
      (node (ref "R8") (pin "1") (pinfunction "1_1") (pintype "passive"))
    )
    (net (code "54") (name "Net-(LED5-PadA)") (class "Default")
      (node (ref "LED5") (pin "A") (pinfunction "A_A") (pintype "passive"))
      (node (ref "R9") (pin "1") (pinfunction "1_1") (pintype "passive"))
    )
    (net (code "55") (name "Net-(LED6-PadA)") (class "Default")
      (node (ref "LED6") (pin "A") (pinfunction "A_A") (pintype "passive"))
      (node (ref "R10") (pin "1") (pinfunction "1_1") (pintype "passive"))
    )
    (net (code "56") (name "Net-(LED7-PadA)") (class "Default")
      (node (ref "LED7") (pin "A") (pinfunction "A_A") (pintype "passive"))
      (node (ref "R11") (pin "1") (pinfunction "1_1") (pintype "passive"))
    )
    (net (code "57") (name "Net-(LED8-PadA)") (class "Default")
      (node (ref "LED8") (pin "A") (pinfunction "A_A") (pintype "passive"))
      (node (ref "R12") (pin "1") (pinfunction "1_1") (pintype "passive"))
    )
    (net (code "58") (name "Net-(LED9-PadA)") (class "Default")
      (node (ref "LED9") (pin "A") (pinfunction "A_A") (pintype "passive"))
      (node (ref "R13") (pin "1") (pinfunction "1_1") (pintype "passive"))
    )
    (net (code "59") (name "Net-(LED10-PadA)") (class "Default")
      (node (ref "LED10") (pin "A") (pinfunction "A_A") (pintype "passive"))
      (node (ref "R27") (pin "2") (pinfunction "2_2") (pintype "passive"))
    )
    (net (code "60") (name "Net-(LED11-PadA)") (class "Default")
      (node (ref "LED11") (pin "A") (pinfunction "A_A") (pintype "passive"))
      (node (ref "R28") (pin "2") (pinfunction "2_2") (pintype "passive"))
    )
    (net (code "61") (name "Net-(Q2-B)") (class "Default")
      (node (ref "C16") (pin "2") (pinfunction "2_2") (pintype "passive"))
      (node (ref "Q2") (pin "1") (pinfunction "B_1") (pintype "passive"))
      (node (ref "R22") (pin "2") (pinfunction "2_2") (pintype "passive"))
      (node (ref "R24") (pin "2") (pinfunction "2_2") (pintype "passive"))
    )
    (net (code "62") (name "Net-(Q2-C-Pad2)") (class "Default")
      (node (ref "Q2") (pin "2") (pinfunction "C_2") (pintype "passive"))
      (node (ref "Q2") (pin "4") (pinfunction "C_4") (pintype "passive"))
      (node (ref "R1") (pin "2") (pinfunction "2_2") (pintype "passive"))
    )
    (net (code "63") (name "Net-(Q3-B)") (class "Default")
      (node (ref "Q3") (pin "1") (pinfunction "B_1") (pintype "passive"))
      (node (ref "R26") (pin "1") (pinfunction "1_1") (pintype "passive"))
      (node (ref "R29") (pin "1") (pinfunction "1_1") (pintype "passive"))
    )
    (net (code "64") (name "Net-(Q3-C)") (class "Default")
      (node (ref "Q3") (pin "3") (pinfunction "C_3") (pintype "passive"))
      (node (ref "R25") (pin "1") (pinfunction "1_1") (pintype "passive"))
    )
    (net (code "65") (name "Net-(Q3-E)") (class "Default")
      (node (ref "Q3") (pin "2") (pinfunction "E_2") (pintype "passive"))
      (node (ref "R1") (pin "1") (pinfunction "1_1") (pintype "passive"))
      (node (ref "R30") (pin "2") (pinfunction "2_2") (pintype "passive"))
    )
    (net (code "66") (name "Net-(R16-Pad1)") (class "Default")
      (node (ref "R16") (pin "1") (pinfunction "1_1") (pintype "passive"))
      (node (ref "SJ1") (pin "2") (pinfunction "2_2") (pintype "passive"))
    )
    (net (code "67") (name "Net-(S1-P)") (class "Default")
      (node (ref "D1") (pin "A") (pinfunction "A_A") (pintype "passive"))
      (node (ref "S1") (pin "3") (pinfunction "P_3") (pintype "passive"))
    )
    (net (code "68") (name "Net-(S2-P)") (class "Default")
      (node (ref "D2") (pin "A") (pinfunction "A_A") (pintype "passive"))
      (node (ref "S2") (pin "3") (pinfunction "P_3") (pintype "passive"))
    )
    (net (code "69") (name "Net-(S3-P)") (class "Default")
      (node (ref "D3") (pin "A") (pinfunction "A_A") (pintype "passive"))
      (node (ref "S3") (pin "3") (pinfunction "P_3") (pintype "passive"))
    )
    (net (code "70") (name "Net-(S4-P)") (class "Default")
      (node (ref "D4") (pin "A") (pinfunction "A_A") (pintype "passive"))
      (node (ref "S4") (pin "3") (pinfunction "P_3") (pintype "passive"))
    )
    (net (code "71") (name "Net-(S5-P)") (class "Default")
      (node (ref "D5") (pin "A") (pinfunction "A_A") (pintype "passive"))
      (node (ref "S5") (pin "3") (pinfunction "P_3") (pintype "passive"))
    )
    (net (code "72") (name "Net-(S6-P)") (class "Default")
      (node (ref "D6") (pin "A") (pinfunction "A_A") (pintype "passive"))
      (node (ref "S6") (pin "3") (pinfunction "P_3") (pintype "passive"))
    )
    (net (code "73") (name "Net-(S7-P)") (class "Default")
      (node (ref "D7") (pin "A") (pinfunction "A_A") (pintype "passive"))
      (node (ref "S7") (pin "3") (pinfunction "P_3") (pintype "passive"))
    )
    (net (code "74") (name "Net-(S8-P)") (class "Default")
      (node (ref "D8") (pin "A") (pinfunction "A_A") (pintype "passive"))
      (node (ref "S8") (pin "3") (pinfunction "P_3") (pintype "passive"))
    )
    (net (code "75") (name "Net-(U1-XTALIN)") (class "Default")
      (node (ref "C18") (pin "2") (pinfunction "2_2") (pintype "passive"))
      (node (ref "C22") (pin "1") (pinfunction "1_1") (pintype "passive"))
      (node (ref "U1") (pin "6") (pinfunction "XTALIN_6") (pintype "input"))
    )
    (net (code "76") (name "Net-(U2-ADJ)") (class "Default")
      (node (ref "C2") (pin "2") (pinfunction "2_2") (pintype "passive"))
      (node (ref "R2") (pin "1") (pinfunction "1_1") (pintype "passive"))
      (node (ref "R5") (pin "2") (pinfunction "2_2") (pintype "passive"))
      (node (ref "U2") (pin "3") (pinfunction "ADJ_3") (pintype "passive"))
    )
    (net (code "77") (name "Net-(U2-BST)") (class "Default")
      (node (ref "C1") (pin "2") (pinfunction "2_2") (pintype "passive"))
      (node (ref "U2") (pin "1") (pinfunction "BST_1") (pintype "output"))
    )
    (net (code "78") (name "Net-(U2-OUT)") (class "Default")
      (node (ref "C1") (pin "1") (pinfunction "1_1") (pintype "passive"))
      (node (ref "D100") (pin "C") (pinfunction "C_C") (pintype "passive"))
      (node (ref "L1") (pin "1") (pinfunction "1_1") (pintype "passive"))
      (node (ref "U2") (pin "6") (pinfunction "OUT_6") (pintype "output"))
    )
    (net (code "79") (name "Net-(U3-FO)") (class "Default")
      (node (ref "C18") (pin "1") (pinfunction "1_1") (pintype "passive"))
      (node (ref "U3") (pin "3") (pinfunction "FO_3") (pintype "output"))
    )
    (net (code "80") (name "unconnected-(LSP1-PadMP)") (class "Default")
      (node (ref "LSP1") (pin "MP") (pinfunction "MP_MP") (pintype "passive"))
    )
    (net (code "81") (name "unconnected-(LSP2-PadMP)") (class "Default")
      (node (ref "LSP2") (pin "MP") (pinfunction "MP_MP") (pintype "passive"))
    )
    (net (code "82") (name "unconnected-(P2-Pad6)") (class "Default")
      (node (ref "P2") (pin "6") (pinfunction "6_6") (pintype "passive"))
    )
    (net (code "83") (name "unconnected-(P2-Pad8)") (class "Default")
      (node (ref "P2") (pin "8") (pinfunction "8_8") (pintype "passive"))
    )
    (net (code "84") (name "unconnected-(S1-P1-Pad4)") (class "Default")
      (node (ref "S1") (pin "4") (pinfunction "P1_4") (pintype "passive"))
    )
    (net (code "85") (name "unconnected-(S1-S1-Pad2)") (class "Default")
      (node (ref "S1") (pin "2") (pinfunction "S1_2") (pintype "passive"))
    )
    (net (code "86") (name "unconnected-(S2-P1-Pad4)") (class "Default")
      (node (ref "S2") (pin "4") (pinfunction "P1_4") (pintype "passive"))
    )
    (net (code "87") (name "unconnected-(S2-S1-Pad2)") (class "Default")
      (node (ref "S2") (pin "2") (pinfunction "S1_2") (pintype "passive"))
    )
    (net (code "88") (name "unconnected-(S3-P1-Pad4)") (class "Default")
      (node (ref "S3") (pin "4") (pinfunction "P1_4") (pintype "passive"))
    )
    (net (code "89") (name "unconnected-(S3-S1-Pad2)") (class "Default")
      (node (ref "S3") (pin "2") (pinfunction "S1_2") (pintype "passive"))
    )
    (net (code "90") (name "unconnected-(S4-P1-Pad4)") (class "Default")
      (node (ref "S4") (pin "4") (pinfunction "P1_4") (pintype "passive"))
    )
    (net (code "91") (name "unconnected-(S4-S1-Pad2)") (class "Default")
      (node (ref "S4") (pin "2") (pinfunction "S1_2") (pintype "passive"))
    )
    (net (code "92") (name "unconnected-(S5-P1-Pad4)") (class "Default")
      (node (ref "S5") (pin "4") (pinfunction "P1_4") (pintype "passive"))
    )
    (net (code "93") (name "unconnected-(S5-S1-Pad2)") (class "Default")
      (node (ref "S5") (pin "2") (pinfunction "S1_2") (pintype "passive"))
    )
    (net (code "94") (name "unconnected-(S6-P1-Pad4)") (class "Default")
      (node (ref "S6") (pin "4") (pinfunction "P1_4") (pintype "passive"))
    )
    (net (code "95") (name "unconnected-(S6-S1-Pad2)") (class "Default")
      (node (ref "S6") (pin "2") (pinfunction "S1_2") (pintype "passive"))
    )
    (net (code "96") (name "unconnected-(S7-P1-Pad4)") (class "Default")
      (node (ref "S7") (pin "4") (pinfunction "P1_4") (pintype "passive"))
    )
    (net (code "97") (name "unconnected-(S7-S1-Pad2)") (class "Default")
      (node (ref "S7") (pin "2") (pinfunction "S1_2") (pintype "passive"))
    )
    (net (code "98") (name "unconnected-(S8-P1-Pad4)") (class "Default")
      (node (ref "S8") (pin "4") (pinfunction "P1_4") (pintype "passive"))
    )
    (net (code "99") (name "unconnected-(S8-S1-Pad2)") (class "Default")
      (node (ref "S8") (pin "2") (pinfunction "S1_2") (pintype "passive"))
    )
    (net (code "100") (name "unconnected-(S9-P1-Pad4)") (class "Default")
      (node (ref "S9") (pin "4") (pinfunction "P1_4") (pintype "passive"))
    )
    (net (code "101") (name "unconnected-(S9-S-Pad1)") (class "Default")
      (node (ref "S9") (pin "1") (pinfunction "S_1") (pintype "passive"))
    )
    (net (code "102") (name "unconnected-(S10-P1-Pad4)") (class "Default")
      (node (ref "S10") (pin "4") (pinfunction "P1_4") (pintype "passive"))
    )
    (net (code "103") (name "unconnected-(S10-S-Pad1)") (class "Default")
      (node (ref "S10") (pin "1") (pinfunction "S_1") (pintype "passive"))
    )
    (net (code "104") (name "unconnected-(U1-PIO2_6{slash}CT32B0_MAT1-Pad1)") (class "Default")
      (node (ref "U1") (pin "1") (pinfunction "PIO2_6/CT32B0_MAT1_1") (pintype "bidirectional"))
    )
    (net (code "105") (name "unconnected-(U1-PIO2_7{slash}CT32B0_MAT2{slash}RXD-Pad11)") (class "Default")
      (node (ref "U1") (pin "11") (pinfunction "PIO2_7/CT32B0_MAT2/RXD_11") (pintype "bidirectional"))
    )
    (net (code "106") (name "unconnected-(U1-PIO3_3{slash}RI{slash}CT16B0_CAP0-Pad48)") (class "Default")
      (node (ref "U1") (pin "48") (pinfunction "PIO3_3/RI/CT16B0_CAP0_48") (pintype "bidirectional"))
    )
    (net (code "107") (name "unconnected-(U1-XTALOUT-Pad7)") (class "Default")
      (node (ref "U1") (pin "7") (pinfunction "XTALOUT_7") (pintype "output"))
    )
  )
)
